# ptw-wheel.net
KiCad netlist of a schematic drawn in EAGLE
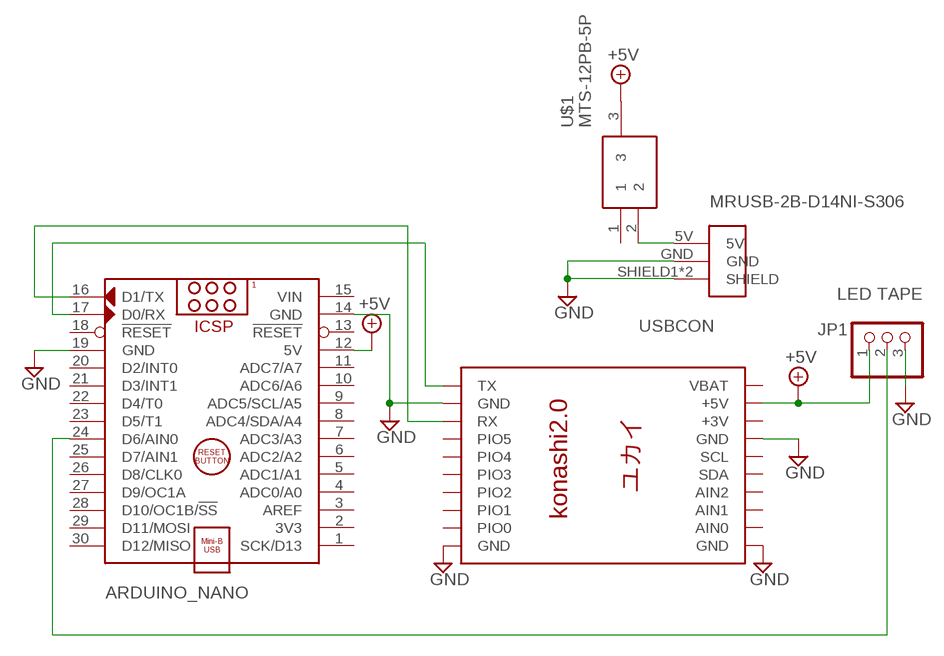
[diagram p0: schematic, sheet 1]

(export (version "E")
  (design (tool "Eeschema 10.0.6"))
  (components
    (comp (ref "ARDUINO_NANO")
      (value "ARDUINO_NANO")
      (footprint "eagle-import:ARDUINO_NANO")
      (libsource (lib "eagle-import") (part "ARDUINO_NANO"))
    )
    (comp (ref "JP1")
      (value "LED TAPE")
      (footprint "eagle-import:1X03")
      (libsource (lib "eagle-import") (part "PINHD-1X3"))
    )
    (comp (ref "KONASHI")
      (value "KONASHI2.0")
      (footprint "eagle-import:KONASHI")
      (libsource (lib "eagle-import") (part "KONASHI2.0"))
    )
    (comp (ref "MRUSB-2B-D14NI-S306")
      (value "USBCON")
      (footprint "eagle-import:USBCON")
      (libsource (lib "eagle-import") (part "USBCON"))
    )
    (comp (ref "U$1")
      (value "MTS-12PB-5P")
      (footprint "eagle-import:MTS-12PB-5P")
      (libsource (lib "eagle-import") (part "MTS-12PB-5P"))
    )
  )
  (nets
    (net (code "1") (name "+5V") (class "Default")
      (node (ref "ARDUINO_NANO") (pin "12") (pinfunction "5V_12") (pintype "power_in"))
      (node (ref "JP1") (pin "1") (pinfunction "1_1") (pintype "passive"))
      (node (ref "KONASHI") (pin "+5V") (pinfunction "+5V_+5V") (pintype "power_in"))
      (node (ref "U$1") (pin "3") (pinfunction "3_3") (pintype "bidirectional"))
    )
    (net (code "2") (name "/+3V") (class "Default")
      (node (ref "KONASHI") (pin "+3V") (pinfunction "+3V_+3V") (pintype "power_in"))
    )
    (net (code "3") (name "/VBAT") (class "Default")
      (node (ref "KONASHI") (pin "VBAT") (pinfunction "VBAT_VBAT") (pintype "power_in"))
    )
    (net (code "4") (name "/VIN") (class "Default")
      (node (ref "ARDUINO_NANO") (pin "15") (pinfunction "VIN_15") (pintype "power_in"))
    )
    (net (code "5") (name "GND") (class "Default")
      (node (ref "ARDUINO_NANO") (pin "14") (pinfunction "GND_14") (pintype "power_in"))
      (node (ref "ARDUINO_NANO") (pin "19") (pinfunction "GND_19") (pintype "power_in"))
      (node (ref "JP1") (pin "3") (pinfunction "3_3") (pintype "passive"))
      (node (ref "KONASHI") (pin "GND") (pinfunction "GND_GND") (pintype "power_in"))
      (node (ref "KONASHI") (pin "GND@1") (pinfunction "GND_GND@1") (pintype "power_in"))
      (node (ref "KONASHI") (pin "GND@2") (pinfunction "GND_GND@2") (pintype "passive"))
      (node (ref "KONASHI") (pin "GND@3") (pinfunction "GND_GND@3") (pintype "bidirectional"))
      (node (ref "MRUSB-2B-D14NI-S306") (pin "GND") (pinfunction "GND_GND") (pintype "passive"))
      (node (ref "MRUSB-2B-D14NI-S306") (pin "SHIELD1") (pinfunction "SHIELD_SHIELD1") (pintype "passive"))
      (node (ref "MRUSB-2B-D14NI-S306") (pin "SHIELD2") (pinfunction "SHIELD_SHIELD2") (pintype "passive"))
    )
    (net (code "6") (name "Net-(ARDUINO_NANO-D0{slash}RX)") (class "Default")
      (node (ref "ARDUINO_NANO") (pin "17") (pinfunction "D0/RX_17") (pintype "bidirectional"))
      (node (ref "KONASHI") (pin "TX") (pinfunction "TX_TX") (pintype "bidirectional"))
    )
    (net (code "7") (name "Net-(ARDUINO_NANO-D1{slash}TX)") (class "Default")
      (node (ref "ARDUINO_NANO") (pin "16") (pinfunction "D1/TX_16") (pintype "bidirectional"))
      (node (ref "KONASHI") (pin "RX") (pinfunction "RX_RX") (pintype "bidirectional"))
    )
    (net (code "8") (name "Net-(ARDUINO_NANO-D6{slash}AIN0)") (class "Default")
      (node (ref "ARDUINO_NANO") (pin "24") (pinfunction "D6/AIN0_24") (pintype "bidirectional"))
      (node (ref "JP1") (pin "2") (pinfunction "2_2") (pintype "passive"))
    )
    (net (code "9") (name "Net-(MRUSB-2B-D14NI-S306-Pad5V)") (class "Default")
      (node (ref "MRUSB-2B-D14NI-S306") (pin "5V") (pinfunction "5V_5V") (pintype "passive"))
      (node (ref "U$1") (pin "2") (pinfunction "2_2") (pintype "bidirectional"))
    )
    (net (code "10") (name "unconnected-(ARDUINO_NANO-3V3-Pad2)") (class "Default")
      (node (ref "ARDUINO_NANO") (pin "2") (pinfunction "3V3_2") (pintype "output"))
    )
    (net (code "11") (name "unconnected-(ARDUINO_NANO-ADC0{slash}A0-Pad4)") (class "Default")
      (node (ref "ARDUINO_NANO") (pin "4") (pinfunction "ADC0/A0_4") (pintype "bidirectional"))
    )
    (net (code "12") (name "unconnected-(ARDUINO_NANO-ADC1{slash}A1-Pad5)") (class "Default")
      (node (ref "ARDUINO_NANO") (pin "5") (pinfunction "ADC1/A1_5") (pintype "bidirectional"))
    )
    (net (code "13") (name "unconnected-(ARDUINO_NANO-ADC2{slash}A2-Pad6)") (class "Default")
      (node (ref "ARDUINO_NANO") (pin "6") (pinfunction "ADC2/A2_6") (pintype "bidirectional"))
    )
    (net (code "14") (name "unconnected-(ARDUINO_NANO-ADC3{slash}A3-Pad7)") (class "Default")
      (node (ref "ARDUINO_NANO") (pin "7") (pinfunction "ADC3/A3_7") (pintype "bidirectional"))
    )
    (net (code "15") (name "unconnected-(ARDUINO_NANO-ADC4{slash}SDA{slash}A4-Pad8)") (class "Default")
      (node (ref "ARDUINO_NANO") (pin "8") (pinfunction "ADC4/SDA/A4_8") (pintype "bidirectional"))
    )
    (net (code "16") (name "unconnected-(ARDUINO_NANO-ADC5{slash}SCL{slash}A5-Pad9)") (class "Default")
      (node (ref "ARDUINO_NANO") (pin "9") (pinfunction "ADC5/SCL/A5_9") (pintype "bidirectional"))
    )
    (net (code "17") (name "unconnected-(ARDUINO_NANO-ADC6{slash}A6-Pad10)") (class "Default")
      (node (ref "ARDUINO_NANO") (pin "10") (pinfunction "ADC6/A6_10") (pintype "bidirectional"))
    )
    (net (code "18") (name "unconnected-(ARDUINO_NANO-ADC7{slash}A7-Pad11)") (class "Default")
      (node (ref "ARDUINO_NANO") (pin "11") (pinfunction "ADC7/A7_11") (pintype "bidirectional"))
    )
    (net (code "19") (name "unconnected-(ARDUINO_NANO-AREF-Pad3)") (class "Default")
      (node (ref "ARDUINO_NANO") (pin "3") (pinfunction "AREF_3") (pintype "input"))
    )
    (net (code "20") (name "unconnected-(ARDUINO_NANO-D2{slash}INT0-Pad20)") (class "Default")
      (node (ref "ARDUINO_NANO") (pin "20") (pinfunction "D2/INT0_20") (pintype "bidirectional"))
    )
    (net (code "21") (name "unconnected-(ARDUINO_NANO-D3{slash}INT1-Pad21)") (class "Default")
      (node (ref "ARDUINO_NANO") (pin "21") (pinfunction "D3/INT1_21") (pintype "bidirectional"))
    )
    (net (code "22") (name "unconnected-(ARDUINO_NANO-D4{slash}T0-Pad22)") (class "Default")
      (node (ref "ARDUINO_NANO") (pin "22") (pinfunction "D4/T0_22") (pintype "bidirectional"))
    )
    (net (code "23") (name "unconnected-(ARDUINO_NANO-D5{slash}T1-Pad23)") (class "Default")
      (node (ref "ARDUINO_NANO") (pin "23") (pinfunction "D5/T1_23") (pintype "bidirectional"))
    )
    (net (code "24") (name "unconnected-(ARDUINO_NANO-D7{slash}AIN1-Pad25)") (class "Default")
      (node (ref "ARDUINO_NANO") (pin "25") (pinfunction "D7/AIN1_25") (pintype "bidirectional"))
    )
    (net (code "25") (name "unconnected-(ARDUINO_NANO-D8{slash}CLK0-Pad26)") (class "Default")
      (node (ref "ARDUINO_NANO") (pin "26") (pinfunction "D8/CLK0_26") (pintype "bidirectional"))
    )
    (net (code "26") (name "unconnected-(ARDUINO_NANO-D9{slash}OC1A-Pad27)") (class "Default")
      (node (ref "ARDUINO_NANO") (pin "27") (pinfunction "D9/OC1A_27") (pintype "bidirectional"))
    )
    (net (code "27") (name "unconnected-(ARDUINO_NANO-D10{slash}OC1B{slash}~{SS}-Pad28)") (class "Default")
      (node (ref "ARDUINO_NANO") (pin "28") (pinfunction "D10/OC1B/~{SS}_28") (pintype "bidirectional"))
    )
    (net (code "28") (name "unconnected-(ARDUINO_NANO-D11{slash}MOSI-Pad29)") (class "Default")
      (node (ref "ARDUINO_NANO") (pin "29") (pinfunction "D11/MOSI_29") (pintype "bidirectional"))
    )
    (net (code "29") (name "unconnected-(ARDUINO_NANO-D12{slash}MISO-Pad30)") (class "Default")
      (node (ref "ARDUINO_NANO") (pin "30") (pinfunction "D12/MISO_30") (pintype "bidirectional"))
    )
    (net (code "30") (name "unconnected-(ARDUINO_NANO-SCK{slash}D13-Pad1)") (class "Default")
      (node (ref "ARDUINO_NANO") (pin "1") (pinfunction "SCK/D13_1") (pintype "bidirectional"))
    )
    (net (code "31") (name "unconnected-(ARDUINO_NANO-~{RESET}-Pad13)") (class "Default")
      (node (ref "ARDUINO_NANO") (pin "13") (pinfunction "~{RESET}_13") (pintype "input"))
    )
    (net (code "32") (name "unconnected-(ARDUINO_NANO-~{RESET}-Pad18)") (class "Default")
      (node (ref "ARDUINO_NANO") (pin "18") (pinfunction "~{RESET}_18") (pintype "input"))
    )
    (net (code "33") (name "unconnected-(KONASHI-AIN0-PadAIO0)") (class "Default")
      (node (ref "KONASHI") (pin "AIO0") (pinfunction "AIN0_AIO0") (pintype "bidirectional"))
    )
    (net (code "34") (name "unconnected-(KONASHI-AIN1-PadAIO1)") (class "Default")
      (node (ref "KONASHI") (pin "AIO1") (pinfunction "AIN1_AIO1") (pintype "bidirectional"))
    )
    (net (code "35") (name "unconnected-(KONASHI-AIN2-PadAIO2)") (class "Default")
      (node (ref "KONASHI") (pin "AIO2") (pinfunction "AIN2_AIO2") (pintype "bidirectional"))
    )
    (net (code "36") (name "unconnected-(KONASHI-PadPIO0)") (class "Default")
      (node (ref "KONASHI") (pin "PIO0") (pinfunction "PIO0_PIO0") (pintype "bidirectional"))
    )
    (net (code "37") (name "unconnected-(KONASHI-PadPIO1)") (class "Default")
      (node (ref "KONASHI") (pin "PIO1") (pinfunction "PIO1_PIO1") (pintype "bidirectional"))
    )
    (net (code "38") (name "unconnected-(KONASHI-PadPIO2)") (class "Default")
      (node (ref "KONASHI") (pin "PIO2") (pinfunction "PIO2_PIO2") (pintype "bidirectional"))
    )
    (net (code "39") (name "unconnected-(KONASHI-PadPIO3)") (class "Default")
      (node (ref "KONASHI") (pin "PIO3") (pinfunction "PIO3_PIO3") (pintype "bidirectional"))
    )
    (net (code "40") (name "unconnected-(KONASHI-PadPIO4)") (class "Default")
      (node (ref "KONASHI") (pin "PIO4") (pinfunction "PIO4_PIO4") (pintype "bidirectional"))
    )
    (net (code "41") (name "unconnected-(KONASHI-PadPIO5)") (class "Default")
      (node (ref "KONASHI") (pin "PIO5") (pinfunction "PIO5_PIO5") (pintype "bidirectional"))
    )
    (net (code "42") (name "unconnected-(KONASHI-SCL-PadPIO7{slash}SCL)") (class "Default")
      (node (ref "KONASHI") (pin "PIO7/SCL") (pinfunction "SCL_PIO7/SCL") (pintype "bidirectional"))
    )
    (net (code "43") (name "unconnected-(KONASHI-SDA-PadPIO6{slash}SDA)") (class "Default")
      (node (ref "KONASHI") (pin "PIO6/SDA") (pinfunction "SDA_PIO6/SDA") (pintype "bidirectional"))
    )
    (net (code "44") (name "unconnected-(U$1-Pad1)") (class "Default")
      (node (ref "U$1") (pin "1") (pinfunction "1_1") (pintype "bidirectional"))
    )
  )
)
